# SFP_TEMP_EEPROM_GPIO.net
KiCad netlist of a schematic drawn in Altium Designer
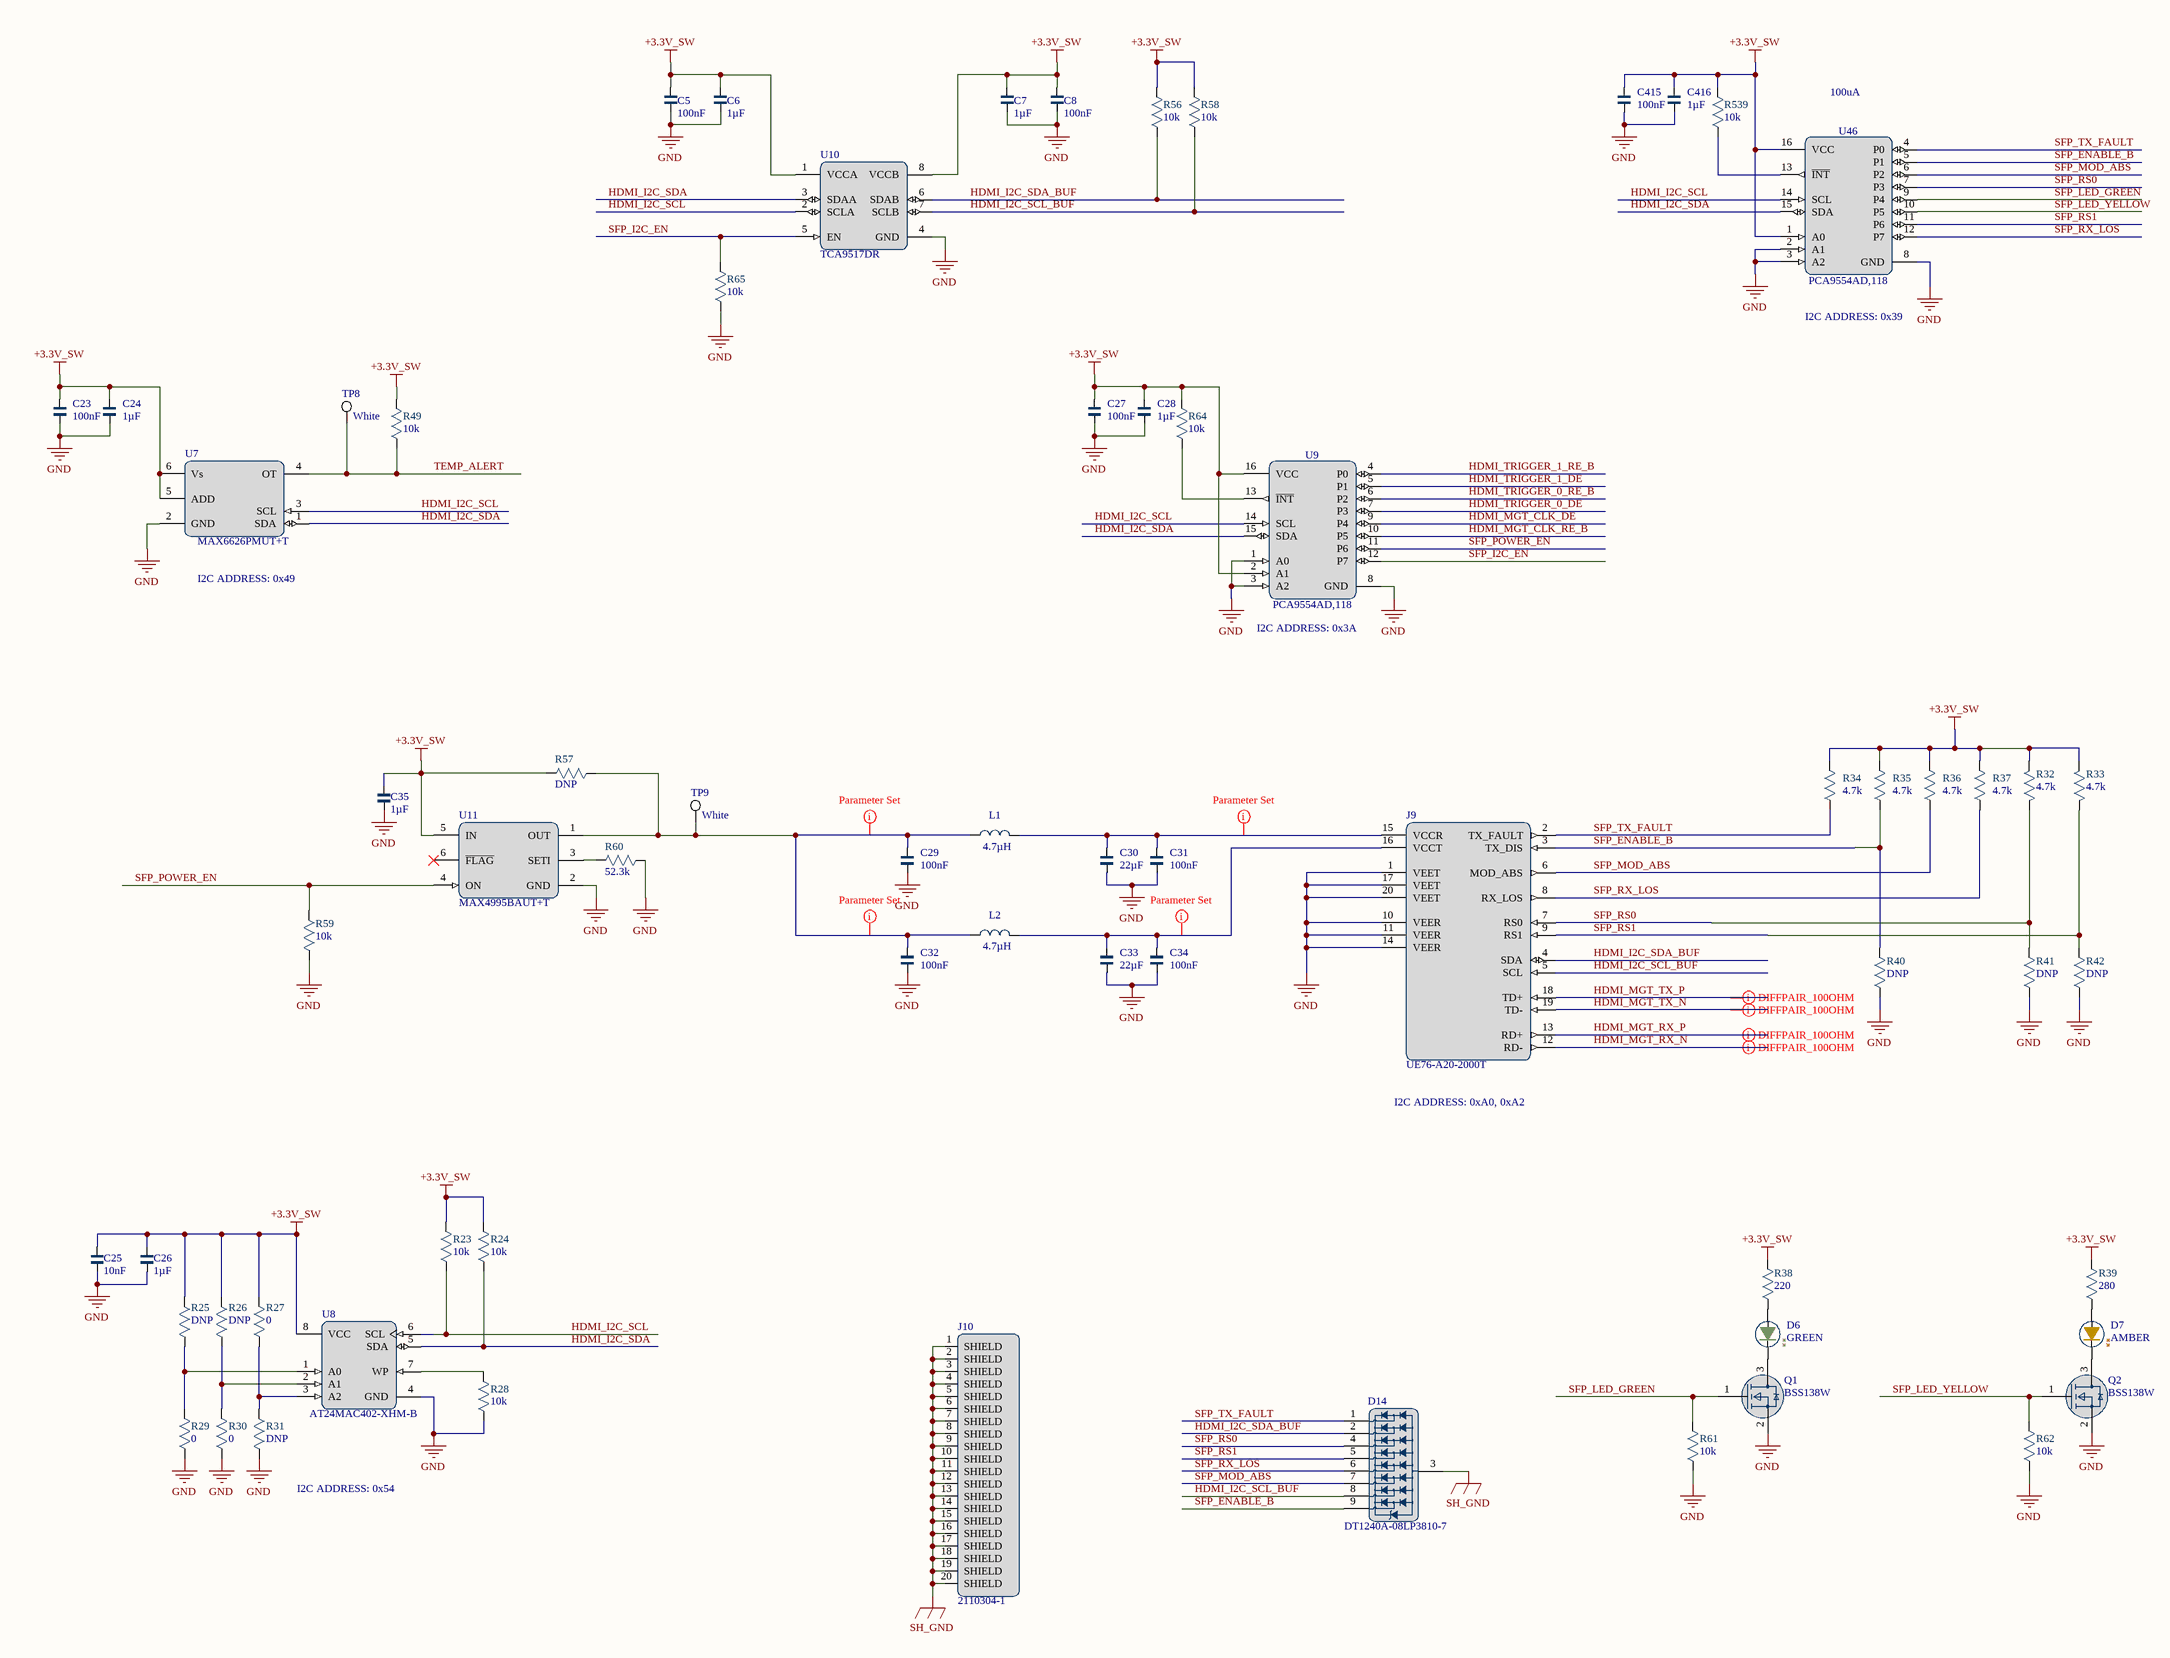
[diagram p0: SFP_TEMP_EEPROM_GPIO.SchDoc]

(export (version "E")
  (design (tool "Eeschema 10.0.6"))
  (components
    (comp (ref "C5")
      (value "100nF")
      (footprint "CAPC160X80X95L35")
      (description "CAP CER 0.1UF 25V X7R 0603")
      (fields (field (name "VOLTAGE") "25V") (field (name "MFG") "Kemet"))
      (libsource (lib "Atom Computing") (part "CAP"))
    )
    (comp (ref "C6")
      (value "1µF")
      (footprint "CAPC160X80X95L35")
      (description "CAP CER 1uF 10V 10% 0603")
      (fields (field (name "VOLTAGE") "10V") (field (name "TOLERANCE") "10%"))
      (libsource (lib "Atom Computing") (part "CAP"))
    )
    (comp (ref "C7")
      (value "1µF")
      (footprint "CAPC160X80X95L35")
      (description "CAP CER 1uF 10V 10% 0603")
      (fields (field (name "VOLTAGE") "10V") (field (name "TOLERANCE") "10%"))
      (libsource (lib "") (part "CAP_1"))
    )
    (comp (ref "C8")
      (value "100nF")
      (footprint "CAPC160X80X95L35")
      (description "CAP CER 0.1UF 25V X7R 0603")
      (fields (field (name "VOLTAGE") "25V") (field (name "MFG") "Kemet"))
      (libsource (lib "") (part "CAP_1"))
    )
    (comp (ref "C23")
      (value "100nF")
      (footprint "CAPC160X80X95L35")
      (description "CAP CER 0.1UF 25V X7R 0603")
      (fields (field (name "VOLTAGE") "25V") (field (name "MFG") "Kemet"))
      (libsource (lib "Atom Computing") (part "CAP"))
    )
    (comp (ref "C24")
      (value "1µF")
      (footprint "CAPC160X80X95L35")
      (description "CAP CER 1uF 10V 10% 0603")
      (fields (field (name "VOLTAGE") "10V") (field (name "TOLERANCE") "10%"))
      (libsource (lib "Atom Computing") (part "CAP"))
    )
    (comp (ref "C25")
      (value "10nF")
      (footprint "CAPC160X80X95L35")
      (description "CAP CER 10000PF 50V C0G 0603")
      (fields (field (name "MFG") "TDK Corporation") (field (name "TOLERANCE") "5%"))
      (libsource (lib "Atom Computing") (part "CAP"))
    )
    (comp (ref "C26")
      (value "1µF")
      (footprint "CAPC160X80X95L35")
      (description "CAP CER 1uF 10V 10% 0603")
      (fields (field (name "MFG") "Kemet") (field (name "TOLERANCE") "10%"))
      (libsource (lib "Atom Computing") (part "CAP"))
    )
    (comp (ref "C27")
      (value "100nF")
      (footprint "CAPC160X80X95L35")
      (description "CAP CER 0.1UF 25V X7R 0603")
      (fields (field (name "VOLTAGE") "25V") (field (name "MFG") "Kemet"))
      (libsource (lib "Atom Computing") (part "CAP"))
    )
    (comp (ref "C28")
      (value "1µF")
      (footprint "CAPC160X80X95L35")
      (description "CAP CER 1uF 10V 10% 0603")
      (fields (field (name "VOLTAGE") "10V") (field (name "TOLERANCE") "10%"))
      (libsource (lib "Atom Computing") (part "CAP"))
    )
    (comp (ref "C29")
      (value "100nF")
      (footprint "CAPC160X80X95L35")
      (description "CAP CER 0.1UF 25V X7R 0603")
      (fields (field (name "MFG") "Kemet") (field (name "TOLERANCE") "10%"))
      (libsource (lib "Atom Computing") (part "CAP"))
    )
    (comp (ref "C30")
      (value "22µF")
      (footprint "CAPC320X160X90L50")
      (description "CAP CER 22UF 10V X7R 1206")
      (fields (field (name "MFG") "MURATA") (field (name "TOLERANCE") "10%"))
      (libsource (lib "Atom Computing") (part "CAP"))
    )
    (comp (ref "C31")
      (value "100nF")
      (footprint "CAPC160X80X95L35")
      (description "CAP CER 0.1UF 25V X7R 0603")
      (fields (field (name "MFG") "Kemet") (field (name "TOLERANCE") "10%"))
      (libsource (lib "Atom Computing") (part "CAP"))
    )
    (comp (ref "C32")
      (value "100nF")
      (footprint "CAPC160X80X95L35")
      (description "CAP CER 0.1UF 25V X7R 0603")
      (fields (field (name "MFG") "Kemet") (field (name "TOLERANCE") "10%"))
      (libsource (lib "Atom Computing") (part "CAP"))
    )
    (comp (ref "C33")
      (value "22µF")
      (footprint "CAPC320X160X90L50")
      (description "CAP CER 22UF 10V X7R 1206")
      (fields (field (name "MFG") "MURATA") (field (name "TOLERANCE") "10%"))
      (libsource (lib "Atom Computing") (part "CAP"))
    )
    (comp (ref "C34")
      (value "100nF")
      (footprint "CAPC160X80X95L35")
      (description "CAP CER 0.1UF 25V X7R 0603")
      (fields (field (name "MFG") "Kemet") (field (name "TOLERANCE") "10%"))
      (libsource (lib "Atom Computing") (part "CAP"))
    )
    (comp (ref "C35")
      (value "1µF")
      (footprint "CAPC160X80X95L35")
      (description "CAP CER 1uF 10V 10% 0603")
      (fields (field (name "MFG") "Kemet") (field (name "TOLERANCE") "10%"))
      (libsource (lib "Atom Computing") (part "CAP"))
    )
    (comp (ref "C415")
      (value "100nF")
      (footprint "CAPC160X80X95L35")
      (description "CAP CER 0.1UF 25V X7R 0603")
      (fields (field (name "MFG") "Kemet") (field (name "TOLERANCE") "10%"))
      (libsource (lib "Atom Computing") (part "CAP"))
    )
    (comp (ref "C416")
      (value "1µF")
      (footprint "CAPC160X80X95L35")
      (description "±10% 35V Ceramic Capacitor X7R 0603 (1608 Metric)")
      (fields (field (name "MFG") "TDK Corporation"))
      (libsource (lib "") (part "CAP_2"))
    )
    (comp (ref "D6")
      (value "GREEN")
      (footprint "BROADCOM_HSMX-C120")
      (description "LED GREEN CLEAR CHIP SMD R/A")
      (fields (field (name "MFG") "AVAGO TECHNOLOGIES"))
      (libsource (lib "Atom Computing") (part "LED_GREEN"))
    )
    (comp (ref "D7")
      (value "AMBER")
      (footprint "BROADCOM_HSMX-C120")
      (description "LED AMBER CLEAR CHIP SMD R/A 0603")
      (fields (field (name "MFG") "Broadcom Limited"))
      (libsource (lib "Atom Computing") (part "LED_AMBER"))
    )
    (comp (ref "D14")
      (value "DT1240A-08LP3810-7")
      (footprint "DIODES_DT1240A-08LP3810-7")
      (description "TVS DIODE 3.3VWM 10V U-DFN3810-9")
      (fields (field (name "MFG") "Diodes Incorporated"))
      (libsource (lib "Atom Computing") (part "DT1240A-08LP3810-7"))
    )
    (comp (ref "J9")
      (value "UE76-A20-2000T")
      (footprint "AMPHENOL_UX76-A20-X00XX")
      (description "20 Position SFP+ Receptacle Connector Solder Surface Mount, Right Angle")
      (fields (field (name "MFG") "Amphenol ICC (Commercial Products)"))
      (libsource (lib "Atom Computing") (part "SFP+ Connector"))
    )
    (comp (ref "J10")
      (value "2110304-1")
      (footprint "TE_2110304-1_NO_KEEPOUT")
      (description "Position SFP+ Cage Connector Solder Through Hole, Right Angle")
      (fields (field (name "MFG") "TE Connectivity AMP Connectors"))
      (libsource (lib "Atom Computing") (part "2110304-1"))
    )
    (comp (ref "L1")
      (value "4.7µH")
      (footprint "VISHAY_IHLP-2020BZ")
      (description "FIXED IND 4.7UH 3.2A 81.3 MOHM")
      (fields (field (name "MFG") "Vishay Dale") (field (name "TOLERANCE") "20%"))
      (libsource (lib "Atom Computing") (part "IND"))
    )
    (comp (ref "L2")
      (value "4.7µH")
      (footprint "VISHAY_IHLP-2020BZ")
      (description "FIXED IND 4.7UH 3.2A 81.3 MOHM")
      (fields (field (name "MFG") "Vishay Dale") (field (name "TOLERANCE") "20%"))
      (libsource (lib "Atom Computing") (part "IND"))
    )
    (comp (ref "Q1")
      (value "BSS138W")
      (footprint "SOT23-3P65_210X110L36X22")
      (description "MOSFET N-CH 50V 210MA SC70")
      (fields (field (name "VOLTAGE") "50V") (field (name "MFG") "ON SEMICONDUCTOR"))
      (libsource (lib "Atom Computing") (part "FET_N_3PIN"))
    )
    (comp (ref "Q2")
      (value "BSS138W")
      (footprint "SOT23-3P65_210X110L36X22")
      (description "MOSFET N-CH 50V 210MA SC70")
      (fields (field (name "VOLTAGE") "50V") (field (name "MFG") "ON SEMICONDUCTOR"))
      (libsource (lib "Atom Computing") (part "FET_N_3PIN"))
    )
    (comp (ref "R23")
      (value "10k")
      (footprint "RESC160X85X55L30")
      (description "RES SMD 10K OHM 1% 1/10W 0603")
      (fields (field (name "MFG") "Panasonic Electronic Components") (field (name "POWER") "100mW"))
      (libsource (lib "Atom Computing") (part "RES"))
    )
    (comp (ref "R24")
      (value "10k")
      (footprint "RESC160X85X55L30")
      (description "RES SMD 10K OHM 1% 1/10W 0603")
      (fields (field (name "MFG") "Panasonic Electronic Components") (field (name "POWER") "100mW"))
      (libsource (lib "Atom Computing") (part "RES"))
    )
    (comp (ref "R25")
      (value "DNP")
      (footprint "RESC160X85X55L30")
      (description "DNP, RES 0603")
      (libsource (lib "Atom Computing") (part "RES"))
    )
    (comp (ref "R26")
      (value "DNP")
      (footprint "RESC160X85X55L30")
      (description "DNP, RES 0603")
      (libsource (lib "Atom Computing") (part "RES"))
    )
    (comp (ref "R27")
      (value "0")
      (footprint "RESC160X85X55L30")
      (description "RES 0 OHM JUMPER 1/10W 0603")
      (fields (field (name "MFG") "Yageo"))
      (libsource (lib "Atom Computing") (part "RES"))
    )
    (comp (ref "R28")
      (value "10k")
      (footprint "RESC160X85X55L30")
      (description "RES SMD 10K OHM 1% 1/10W 0603")
      (fields (field (name "MFG") "Panasonic Electronic Components") (field (name "POWER") "100mW"))
      (libsource (lib "Atom Computing") (part "RES"))
    )
    (comp (ref "R29")
      (value "0")
      (footprint "RESC160X85X55L30")
      (description "RES 0 OHM JUMPER 1/10W 0603")
      (fields (field (name "MFG") "Yageo"))
      (libsource (lib "Atom Computing") (part "RES"))
    )
    (comp (ref "R30")
      (value "0")
      (footprint "RESC160X85X55L30")
      (description "RES 0 OHM JUMPER 1/10W 0603")
      (fields (field (name "MFG") "Yageo"))
      (libsource (lib "Atom Computing") (part "RES"))
    )
    (comp (ref "R31")
      (value "DNP")
      (footprint "RESC160X85X55L30")
      (description "DNP, RES 0603")
      (libsource (lib "Atom Computing") (part "RES"))
    )
    (comp (ref "R32")
      (value "4.7k")
      (footprint "RESC160X85X55L30")
      (description "RES SMD 4.7K OHM 1% 1/10W 0603")
      (fields (field (name "MFG") "Yageo"))
      (libsource (lib "Atom Computing") (part "RES"))
    )
    (comp (ref "R33")
      (value "4.7k")
      (footprint "RESC160X85X55L30")
      (description "RES SMD 4.7K OHM 1% 1/10W 0603")
      (fields (field (name "MFG") "Yageo"))
      (libsource (lib "Atom Computing") (part "RES"))
    )
    (comp (ref "R34")
      (value "4.7k")
      (footprint "RESC160X85X55L30")
      (description "RES SMD 4.7K OHM 1% 1/10W 0603")
      (fields (field (name "MFG") "Yageo"))
      (libsource (lib "Atom Computing") (part "RES"))
    )
    (comp (ref "R35")
      (value "4.7k")
      (footprint "RESC160X85X55L30")
      (description "RES SMD 4.7K OHM 1% 1/10W 0603")
      (fields (field (name "MFG") "Yageo"))
      (libsource (lib "Atom Computing") (part "RES"))
    )
    (comp (ref "R36")
      (value "4.7k")
      (footprint "RESC160X85X55L30")
      (description "RES SMD 4.7K OHM 1% 1/10W 0603")
      (fields (field (name "MFG") "Yageo"))
      (libsource (lib "Atom Computing") (part "RES"))
    )
    (comp (ref "R37")
      (value "4.7k")
      (footprint "RESC160X85X55L30")
      (description "RES SMD 4.7K OHM 1% 1/10W 0603")
      (fields (field (name "MFG") "Yageo"))
      (libsource (lib "Atom Computing") (part "RES"))
    )
    (comp (ref "R38")
      (value "220")
      (footprint "RESC160X85X55L30")
      (description "RES SMD 220 OHM 1% 1/10W 0603")
      (fields (field (name "MFG") "Yageo"))
      (libsource (lib "Atom Computing") (part "RES"))
    )
    (comp (ref "R39")
      (value "280")
      (footprint "RESC160X85X55L30")
      (description "RES SMD 280 OHM 1% 1/10W 0603")
      (fields (field (name "MFG") "Panasonic Electronic Components") (field (name "POWER") "100mW"))
      (libsource (lib "Atom Computing") (part "RES"))
    )
    (comp (ref "R40")
      (value "DNP")
      (footprint "RESC160X85X55L30")
      (description "DNP, RES 0603")
      (libsource (lib "Atom Computing") (part "RES"))
    )
    (comp (ref "R41")
      (value "DNP")
      (footprint "RESC160X85X55L30")
      (description "DNP, RES 0603")
      (libsource (lib "Atom Computing") (part "RES"))
    )
    (comp (ref "R42")
      (value "DNP")
      (footprint "RESC160X85X55L30")
      (description "DNP, RES 0603")
      (libsource (lib "Atom Computing") (part "RES"))
    )
    (comp (ref "R49")
      (value "10k")
      (footprint "RESC160X85X55L30")
      (description "RES SMD 10K OHM 1% 1/10W 0603")
      (fields (field (name "MFG") "Panasonic Electronic Components") (field (name "POWER") "100mW"))
      (libsource (lib "Atom Computing") (part "RES"))
    )
    (comp (ref "R56")
      (value "10k")
      (footprint "RESC160X85X55L30")
      (description "RES SMD 10K OHM 1% 1/10W 0603")
      (fields (field (name "MFG") "Panasonic Electronic Components") (field (name "POWER") "100mW"))
      (libsource (lib "Atom Computing") (part "RES"))
    )
    (comp (ref "R57")
      (value "DNP")
      (footprint "RESC160X85X55L30")
      (description "DNP, RES 0603")
      (libsource (lib "Atom Computing") (part "RES"))
    )
    (comp (ref "R58")
      (value "10k")
      (footprint "RESC160X85X55L30")
      (description "RES SMD 10K OHM 1% 1/10W 0603")
      (fields (field (name "MFG") "Panasonic Electronic Components") (field (name "POWER") "100mW"))
      (libsource (lib "Atom Computing") (part "RES"))
    )
    (comp (ref "R59")
      (value "10k")
      (footprint "RESC160X85X55L30")
      (description "RES SMD 10K OHM 1% 1/10W 0603")
      (fields (field (name "MFG") "Panasonic Electronic Components") (field (name "POWER") "100mW"))
      (libsource (lib "Atom Computing") (part "RES"))
    )
    (comp (ref "R60")
      (value "52.3k")
      (footprint "RESC160X85X55L30")
      (description "RES SMD 52.3K 0.1% 1/10W 0603")
      (fields (field (name "MFG") "Yageo"))
      (libsource (lib "Atom Computing") (part "RES"))
    )
    (comp (ref "R61")
      (value "10k")
      (footprint "RESC160X85X55L30")
      (description "RES SMD 10K OHM 1% 1/10W 0603")
      (fields (field (name "MFG") "Panasonic Electronic Components") (field (name "POWER") "100mW"))
      (libsource (lib "Atom Computing") (part "RES"))
    )
    (comp (ref "R62")
      (value "10k")
      (footprint "RESC160X85X55L30")
      (description "RES SMD 10K OHM 1% 1/10W 0603")
      (fields (field (name "MFG") "Panasonic Electronic Components") (field (name "POWER") "100mW"))
      (libsource (lib "Atom Computing") (part "RES"))
    )
    (comp (ref "R64")
      (value "10k")
      (footprint "RESC160X85X55L30")
      (description "RES SMD 10K OHM 1% 1/10W 0603")
      (fields (field (name "MFG") "Panasonic Electronic Components") (field (name "POWER") "100mW"))
      (libsource (lib "Atom Computing") (part "RES"))
    )
    (comp (ref "R65")
      (value "10k")
      (footprint "RESC160X85X55L30")
      (description "RES SMD 10K OHM 1% 1/10W 0603")
      (fields (field (name "MFG") "Panasonic Electronic Components") (field (name "POWER") "100mW"))
      (libsource (lib "Atom Computing") (part "RES"))
    )
    (comp (ref "R539")
      (value "10k")
      (footprint "RESC160X85X55L30")
      (description "RES SMD 10K OHM 1% 1/10W 0603")
      (fields (field (name "MFG") "Panasonic Electronic Components") (field (name "POWER") "100mW"))
      (libsource (lib "Atom Computing") (part "RES"))
    )
    (comp (ref "TP8")
      (value "White")
      (footprint "Keystone_5002")
      (description "Test Point, White, 1-Pin THD, RoHS, Bulk")
      (fields (field (name "MFG") "Keystone"))
      (libsource (lib "Atom Computing") (part "TP_WHITE"))
    )
    (comp (ref "TP9")
      (value "White")
      (footprint "Keystone_5002")
      (description "Test Point, White, 1-Pin THD, RoHS, Bulk")
      (fields (field (name "MFG") "Keystone"))
      (libsource (lib "Atom Computing") (part "TP_WHITE"))
    )
    (comp (ref "U7")
      (value "MAX6626PMUT+T")
      (footprint "SOT23-6P95_280X145L45X42")
      (description "Temperature Sensor Digital, Local -55°C ~ 125°C 12 b SOT-6")
      (fields (field (name "MFG") "Maxim"))
      (libsource (lib "Atom Computing") (part "MAX6626xxUT"))
    )
    (comp (ref "U8")
      (value "AT24MAC402-XHM-B")
      (footprint "SOP8P65_300X640X120L60X24")
      (description "IC EEPROM  MAC 48 2KBIT I2C 1MHZ 8TSSOP")
      (fields (field (name "MFG") "Microchip Technology"))
      (libsource (lib "Atom Computing") (part "AT24MAC402_8PIN"))
    )
    (comp (ref "U9")
      (value "PCA9554AD,118")
      (footprint "SOIC16P127_1030X1032X265L83X42")
      (description "I/O GPIO Expander 8 I2C, SMBus 400 kHz 16-SO")
      (fields (field (name "MFG") "NXP USA Inc."))
      (libsource (lib "Atom Computing") (part "PCA9554xD/PW"))
    )
    (comp (ref "U10")
      (value "TCA9517DR")
      (footprint "SOIC8P127_490X599X175L84X41")
      (description "Voltage Level Translator Bidirectional 1 Circuit 2 Channel 8-SOIC")
      (fields (field (name "MFG") "Texas Instruments"))
      (libsource (lib "Atom Computing") (part "TCA9517"))
    )
    (comp (ref "U11")
      (value "MAX4995BAUT+T")
      (footprint "SOT23-6P95_280X145L45X42")
      (description "IC CURRENT SWITCH ADJ 10% SOT-23-6")
      (fields (field (name "MFG") "Analog Devices Inc./Maxim Integrated"))
      (libsource (lib "Atom Computing") (part "MAX4995xAUT"))
    )
    (comp (ref "U46")
      (value "PCA9554AD,118")
      (footprint "SOIC16P127_1030X1032X265L83X42")
      (description "I/O GPIO Expander 8 I2C, SMBus 400 kHz 16-SO")
      (fields (field (name "MFG") "NXP USA Inc."))
      (libsource (lib "Atom Computing") (part "PCA9554xD/PW"))
    )
  )
  (nets
    (net (code "1") (name "+3.3V_SW") (class "Default")
      (node (ref "C23") (pin "1") (pinfunction "1_1") (pintype "passive"))
      (node (ref "C24") (pin "1") (pinfunction "1_1") (pintype "passive"))
      (node (ref "C25") (pin "1") (pinfunction "1_1") (pintype "passive"))
      (node (ref "C26") (pin "1") (pinfunction "1_1") (pintype "passive"))
      (node (ref "C27") (pin "1") (pinfunction "1_1") (pintype "passive"))
      (node (ref "C28") (pin "1") (pinfunction "1_1") (pintype "passive"))
      (node (ref "C35") (pin "1") (pinfunction "1_1") (pintype "passive"))
      (node (ref "C415") (pin "1") (pinfunction "1_1") (pintype "passive"))
      (node (ref "C416") (pin "2") (pinfunction "2_2") (pintype "passive"))
      (node (ref "C5") (pin "1") (pinfunction "1_1") (pintype "passive"))
      (node (ref "C6") (pin "1") (pinfunction "1_1") (pintype "passive"))
      (node (ref "C7") (pin "1") (pinfunction "1_1") (pintype "passive"))
      (node (ref "C8") (pin "1") (pinfunction "1_1") (pintype "passive"))
      (node (ref "R23") (pin "2") (pinfunction "2_2") (pintype "passive"))
      (node (ref "R24") (pin "2") (pinfunction "2_2") (pintype "passive"))
      (node (ref "R25") (pin "1") (pinfunction "1_1") (pintype "passive"))
      (node (ref "R26") (pin "1") (pinfunction "1_1") (pintype "passive"))
      (node (ref "R27") (pin "2") (pinfunction "2_2") (pintype "passive"))
      (node (ref "R32") (pin "2") (pinfunction "2_2") (pintype "passive"))
      (node (ref "R33") (pin "2") (pinfunction "2_2") (pintype "passive"))
      (node (ref "R34") (pin "2") (pinfunction "2_2") (pintype "passive"))
      (node (ref "R35") (pin "2") (pinfunction "2_2") (pintype "passive"))
      (node (ref "R36") (pin "2") (pinfunction "2_2") (pintype "passive"))
      (node (ref "R37") (pin "2") (pinfunction "2_2") (pintype "passive"))
      (node (ref "R38") (pin "2") (pinfunction "2_2") (pintype "passive"))
      (node (ref "R39") (pin "2") (pinfunction "2_2") (pintype "passive"))
      (node (ref "R49") (pin "2") (pinfunction "2_2") (pintype "passive"))
      (node (ref "R539") (pin "2") (pinfunction "2_2") (pintype "passive"))
      (node (ref "R56") (pin "2") (pinfunction "2_2") (pintype "passive"))
      (node (ref "R57") (pin "2") (pinfunction "2_2") (pintype "passive"))
      (node (ref "R58") (pin "2") (pinfunction "2_2") (pintype "passive"))
      (node (ref "R64") (pin "2") (pinfunction "2_2") (pintype "passive"))
      (node (ref "U10") (pin "1") (pinfunction "VCCA_1") (pintype "power_in"))
      (node (ref "U10") (pin "8") (pinfunction "VCCB_8") (pintype "power_in"))
      (node (ref "U11") (pin "5") (pinfunction "IN_5") (pintype "passive"))
      (node (ref "U46") (pin "1") (pinfunction "A0_1") (pintype "input"))
      (node (ref "U46") (pin "16") (pinfunction "VCC_16") (pintype "power_in"))
      (node (ref "U7") (pin "5") (pinfunction "ADD_5") (pintype "passive"))
      (node (ref "U7") (pin "6") (pinfunction "Vs_6") (pintype "power_in"))
      (node (ref "U8") (pin "8") (pinfunction "VCC_8") (pintype "power_in"))
      (node (ref "U9") (pin "16") (pinfunction "VCC_16") (pintype "power_in"))
      (node (ref "U9") (pin "2") (pinfunction "A1_2") (pintype "input"))
    )
    (net (code "2") (name "/HDMI_I2C_SCL") (class "Default")
      (node (ref "R23") (pin "1") (pinfunction "1_1") (pintype "passive"))
      (node (ref "U10") (pin "2") (pinfunction "SCLA_2") (pintype "bidirectional"))
      (node (ref "U46") (pin "14") (pinfunction "SCL_14") (pintype "input"))
      (node (ref "U7") (pin "3") (pinfunction "SCL_3") (pintype "input"))
      (node (ref "U8") (pin "6") (pinfunction "SCL_6") (pintype "input"))
      (node (ref "U9") (pin "14") (pinfunction "SCL_14") (pintype "input"))
    )
    (net (code "3") (name "/HDMI_I2C_SCL_BUF") (class "Default")
      (node (ref "D14") (pin "8") (pinfunction "LINE-4_8") (pintype "passive"))
      (node (ref "J9") (pin "5") (pinfunction "SCL_5") (pintype "input"))
      (node (ref "R58") (pin "1") (pinfunction "1_1") (pintype "passive"))
      (node (ref "U10") (pin "7") (pinfunction "SCLB_7") (pintype "bidirectional"))
    )
    (net (code "4") (name "/HDMI_I2C_SDA") (class "Default")
      (node (ref "R24") (pin "1") (pinfunction "1_1") (pintype "passive"))
      (node (ref "U10") (pin "3") (pinfunction "SDAA_3") (pintype "bidirectional"))
      (node (ref "U46") (pin "15") (pinfunction "SDA_15") (pintype "bidirectional"))
      (node (ref "U7") (pin "1") (pinfunction "SDA_1") (pintype "bidirectional"))
      (node (ref "U8") (pin "5") (pinfunction "SDA_5") (pintype "bidirectional"))
      (node (ref "U9") (pin "15") (pinfunction "SDA_15") (pintype "bidirectional"))
    )
    (net (code "5") (name "/HDMI_I2C_SDA_BUF") (class "Default")
      (node (ref "D14") (pin "2") (pinfunction "LINE-3_2") (pintype "passive"))
      (node (ref "J9") (pin "4") (pinfunction "SDA_4") (pintype "bidirectional"))
      (node (ref "R56") (pin "1") (pinfunction "1_1") (pintype "passive"))
      (node (ref "U10") (pin "6") (pinfunction "SDAB_6") (pintype "bidirectional"))
    )
    (net (code "6") (name "/HDMI_MGT_CLK_DE") (class "Default")
      (node (ref "U9") (pin "9") (pinfunction "P4_9") (pintype "bidirectional"))
    )
    (net (code "7") (name "/HDMI_MGT_CLK_RE_B") (class "Default")
      (node (ref "U9") (pin "10") (pinfunction "P5_10") (pintype "bidirectional"))
    )
    (net (code "8") (name "/HDMI_MGT_RX_N") (class "Default")
      (node (ref "J9") (pin "12") (pinfunction "RD-_12") (pintype "output"))
    )
    (net (code "9") (name "/HDMI_MGT_RX_P") (class "Default")
      (node (ref "J9") (pin "13") (pinfunction "RD+_13") (pintype "output"))
    )
    (net (code "10") (name "/HDMI_MGT_TX_N") (class "Default")
      (node (ref "J9") (pin "19") (pinfunction "TD-_19") (pintype "input"))
    )
    (net (code "11") (name "/HDMI_MGT_TX_P") (class "Default")
      (node (ref "J9") (pin "18") (pinfunction "TD+_18") (pintype "input"))
    )
    (net (code "12") (name "/HDMI_TRIGGER_0_DE") (class "Default")
      (node (ref "U9") (pin "7") (pinfunction "P3_7") (pintype "bidirectional"))
    )
    (net (code "13") (name "/HDMI_TRIGGER_0_RE_B") (class "Default")
      (node (ref "U9") (pin "6") (pinfunction "P2_6") (pintype "bidirectional"))
    )
    (net (code "14") (name "/HDMI_TRIGGER_1_DE") (class "Default")
      (node (ref "U9") (pin "5") (pinfunction "P1_5") (pintype "bidirectional"))
    )
    (net (code "15") (name "/HDMI_TRIGGER_1_RE_B") (class "Default")
      (node (ref "U9") (pin "4") (pinfunction "P0_4") (pintype "bidirectional"))
    )
    (net (code "16") (name "/SFP_ENABLE_B") (class "Default")
      (node (ref "D14") (pin "9") (pinfunction "LINE-2_9") (pintype "passive"))
      (node (ref "J9") (pin "3") (pinfunction "TX_DIS_3") (pintype "input"))
      (node (ref "R35") (pin "1") (pinfunction "1_1") (pintype "passive"))
      (node (ref "R40") (pin "2") (pinfunction "2_2") (pintype "passive"))
      (node (ref "U46") (pin "5") (pinfunction "P1_5") (pintype "bidirectional"))
    )
    (net (code "17") (name "/SFP_I2C_EN") (class "Default")
      (node (ref "R65") (pin "2") (pinfunction "2_2") (pintype "passive"))
      (node (ref "U10") (pin "5") (pinfunction "EN_5") (pintype "input"))
      (node (ref "U9") (pin "12") (pinfunction "P7_12") (pintype "bidirectional"))
    )
    (net (code "18") (name "/SFP_LED_GREEN") (class "Default")
      (node (ref "Q1") (pin "1") (pinfunction "GATE_1") (pintype "passive"))
      (node (ref "R61") (pin "2") (pinfunction "2_2") (pintype "passive"))
      (node (ref "U46") (pin "9") (pinfunction "P4_9") (pintype "bidirectional"))
    )
    (net (code "19") (name "/SFP_LED_YELLOW") (class "Default")
      (node (ref "Q2") (pin "1") (pinfunction "GATE_1") (pintype "passive"))
      (node (ref "R62") (pin "2") (pinfunction "2_2") (pintype "passive"))
      (node (ref "U46") (pin "10") (pinfunction "P5_10") (pintype "bidirectional"))
    )
    (net (code "20") (name "/SFP_MOD_ABS") (class "Default")
      (node (ref "D14") (pin "7") (pinfunction "LINE-5_7") (pintype "passive"))
      (node (ref "J9") (pin "6") (pinfunction "MOD_ABS_6") (pintype "output"))
      (node (ref "R36") (pin "1") (pinfunction "1_1") (pintype "passive"))
      (node (ref "U46") (pin "6") (pinfunction "P2_6") (pintype "bidirectional"))
    )
    (net (code "21") (name "/SFP_POWER_EN") (class "Default")
      (node (ref "R59") (pin "1") (pinfunction "1_1") (pintype "passive"))
      (node (ref "U11") (pin "4") (pinfunction "ON_4") (pintype "input"))
      (node (ref "U9") (pin "11") (pinfunction "P6_11") (pintype "bidirectional"))
    )
    (net (code "22") (name "/SFP_RS0") (class "Default")
      (node (ref "D14") (pin "4") (pinfunction "LINE-6_4") (pintype "passive"))
      (node (ref "J9") (pin "7") (pinfunction "RS0_7") (pintype "input"))
      (node (ref "R32") (pin "1") (pinfunction "1_1") (pintype "passive"))
      (node (ref "R41") (pin "2") (pinfunction "2_2") (pintype "passive"))
      (node (ref "U46") (pin "7") (pinfunction "P3_7") (pintype "bidirectional"))
    )
    (net (code "23") (name "/SFP_RS1") (class "Default")
      (node (ref "D14") (pin "5") (pinfunction "LINE-8_5") (pintype "passive"))
      (node (ref "J9") (pin "9") (pinfunction "RS1_9") (pintype "input"))
      (node (ref "R33") (pin "1") (pinfunction "1_1") (pintype "passive"))
      (node (ref "R42") (pin "2") (pinfunction "2_2") (pintype "passive"))
      (node (ref "U46") (pin "11") (pinfunction "P6_11") (pintype "bidirectional"))
    )
    (net (code "24") (name "/SFP_RX_LOS") (class "Default")
      (node (ref "D14") (pin "6") (pinfunction "LINE-7_6") (pintype "passive"))
      (node (ref "J9") (pin "8") (pinfunction "RX_LOS_8") (pintype "output"))
      (node (ref "R37") (pin "1") (pinfunction "1_1") (pintype "passive"))
      (node (ref "U46") (pin "12") (pinfunction "P7_12") (pintype "bidirectional"))
    )
    (net (code "25") (name "/SFP_TX_FAULT") (class "Default")
      (node (ref "D14") (pin "1") (pinfunction "LINE-1_1") (pintype "passive"))
      (node (ref "J9") (pin "2") (pinfunction "TX_FAULT_2") (pintype "output"))
      (node (ref "R34") (pin "1") (pinfunction "1_1") (pintype "passive"))
      (node (ref "U46") (pin "4") (pinfunction "P0_4") (pintype "bidirectional"))
    )
    (net (code "26") (name "/TEMP_ALERT") (class "Default")
      (node (ref "R49") (pin "1") (pinfunction "1_1") (pintype "passive"))
      (node (ref "TP8") (pin "1") (pinfunction "1_1") (pintype "passive"))
      (node (ref "U7") (pin "4") (pinfunction "OT_4") (pintype "open_collector"))
    )
    (net (code "27") (name "GND") (class "Default")
      (node (ref "C23") (pin "2") (pinfunction "2_2") (pintype "passive"))
      (node (ref "C24") (pin "2") (pinfunction "2_2") (pintype "passive"))
      (node (ref "C25") (pin "2") (pinfunction "2_2") (pintype "passive"))
      (node (ref "C26") (pin "2") (pinfunction "2_2") (pintype "passive"))
      (node (ref "C27") (pin "2") (pinfunction "2_2") (pintype "passive"))
      (node (ref "C28") (pin "2") (pinfunction "2_2") (pintype "passive"))
      (node (ref "C29") (pin "2") (pinfunction "2_2") (pintype "passive"))
      (node (ref "C30") (pin "2") (pinfunction "2_2") (pintype "passive"))
      (node (ref "C31") (pin "2") (pinfunction "2_2") (pintype "passive"))
      (node (ref "C32") (pin "2") (pinfunction "2_2") (pintype "passive"))
      (node (ref "C33") (pin "2") (pinfunction "2_2") (pintype "passive"))
      (node (ref "C34") (pin "2") (pinfunction "2_2") (pintype "passive"))
      (node (ref "C35") (pin "2") (pinfunction "2_2") (pintype "passive"))
      (node (ref "C415") (pin "2") (pinfunction "2_2") (pintype "passive"))
      (node (ref "C416") (pin "1") (pinfunction "1_1") (pintype "passive"))
      (node (ref "C5") (pin "2") (pinfunction "2_2") (pintype "passive"))
      (node (ref "C6") (pin "2") (pinfunction "2_2") (pintype "passive"))
      (node (ref "C7") (pin "2") (pinfunction "2_2") (pintype "passive"))
      (node (ref "C8") (pin "2") (pinfunction "2_2") (pintype "passive"))
      (node (ref "J9") (pin "1") (pinfunction "VEET_1") (pintype "power_in"))
      (node (ref "J9") (pin "10") (pinfunction "VEER_10") (pintype "power_in"))
      (node (ref "J9") (pin "11") (pinfunction "VEER_11") (pintype "power_in"))
      (node (ref "J9") (pin "14") (pinfunction "VEER_14") (pintype "power_in"))
      (node (ref "J9") (pin "17") (pinfunction "VEET_17") (pintype "power_in"))
      (node (ref "J9") (pin "20") (pinfunction "VEET_20") (pintype "power_in"))
      (node (ref "Q1") (pin "2") (pinfunction "SOURCE_2") (pintype "passive"))
      (node (ref "Q2") (pin "2") (pinfunction "SOURCE_2") (pintype "passive"))
      (node (ref "R28") (pin "1") (pinfunction "1_1") (pintype "passive"))
      (node (ref "R29") (pin "1") (pinfunction "1_1") (pintype "passive"))
      (node (ref "R30") (pin "1") (pinfunction "1_1") (pintype "passive"))
      (node (ref "R31") (pin "2") (pinfunction "2_2") (pintype "passive"))
      (node (ref "R40") (pin "1") (pinfunction "1_1") (pintype "passive"))
      (node (ref "R41") (pin "1") (pinfunction "1_1") (pintype "passive"))
      (node (ref "R42") (pin "1") (pinfunction "1_1") (pintype "passive"))
      (node (ref "R59") (pin "2") (pinfunction "2_2") (pintype "passive"))
      (node (ref "R60") (pin "1") (pinfunction "1_1") (pintype "passive"))
      (node (ref "R61") (pin "1") (pinfunction "1_1") (pintype "passive"))
      (node (ref "R62") (pin "1") (pinfunction "1_1") (pintype "passive"))
      (node (ref "R65") (pin "1") (pinfunction "1_1") (pintype "passive"))
      (node (ref "U10") (pin "4") (pinfunction "GND_4") (pintype "power_in"))
      (node (ref "U11") (pin "2") (pinfunction "GND_2") (pintype "passive"))
      (node (ref "U46") (pin "2") (pinfunction "A1_2") (pintype "input"))
      (node (ref "U46") (pin "3") (pinfunction "A2_3") (pintype "input"))
      (node (ref "U46") (pin "8") (pinfunction "GND_8") (pintype "power_in"))
      (node (ref "U7") (pin "2") (pinfunction "GND_2") (pintype "power_in"))
      (node (ref "U8") (pin "4") (pinfunction "GND_4") (pintype "power_in"))
      (node (ref "U9") (pin "1") (pinfunction "A0_1") (pintype "input"))
      (node (ref "U9") (pin "3") (pinfunction "A2_3") (pintype "input"))
      (node (ref "U9") (pin "8") (pinfunction "GND_8") (pintype "power_in"))
    )
    (net (code "28") (name "Net-(D6-Pad2)") (class "Default")
      (node (ref "D6") (pin "2") (pinfunction "2_2") (pintype "passive"))
      (node (ref "R38") (pin "1") (pinfunction "1_1") (pintype "passive"))
    )
    (net (code "29") (name "Net-(D7-Pad2)") (class "Default")
      (node (ref "D7") (pin "2") (pinfunction "2_2") (pintype "passive"))
      (node (ref "R39") (pin "1") (pinfunction "1_1") (pintype "passive"))
    )
    (net (code "30") (name "Net-(J9-VCCR)") (class "Default")
      (node (ref "C30") (pin "1") (pinfunction "1_1") (pintype "passive"))
      (node (ref "C31") (pin "1") (pinfunction "1_1") (pintype "passive"))
      (node (ref "J9") (pin "15") (pinfunction "VCCR_15") (pintype "power_in"))
      (node (ref "L1") (pin "2") (pinfunction "2_2") (pintype "passive"))
    )
    (net (code "31") (name "Net-(J9-VCCT)") (class "Default")
      (node (ref "C33") (pin "1") (pinfunction "1_1") (pintype "passive"))
      (node (ref "C34") (pin "1") (pinfunction "1_1") (pintype "passive"))
      (node (ref "J9") (pin "16") (pinfunction "VCCT_16") (pintype "power_in"))
      (node (ref "L2") (pin "2") (pinfunction "2_2") (pintype "passive"))
    )
    (net (code "32") (name "Net-(Q1-DRAIN)") (class "Default")
      (node (ref "D6") (pin "1") (pinfunction "1_1") (pintype "passive"))
      (node (ref "Q1") (pin "3") (pinfunction "DRAIN_3") (pintype "passive"))
    )
    (net (code "33") (name "Net-(Q2-DRAIN)") (class "Default")
      (node (ref "D7") (pin "1") (pinfunction "1_1") (pintype "passive"))
      (node (ref "Q2") (pin "3") (pinfunction "DRAIN_3") (pintype "passive"))
    )
    (net (code "34") (name "Net-(U8-A0)") (class "Default")
      (node (ref "R25") (pin "2") (pinfunction "2_2") (pintype "passive"))
      (node (ref "R29") (pin "2") (pinfunction "2_2") (pintype "passive"))
      (node (ref "U8") (pin "1") (pinfunction "A0_1") (pintype "input"))
    )
    (net (code "35") (name "Net-(U8-A1)") (class "Default")
      (node (ref "R26") (pin "2") (pinfunction "2_2") (pintype "passive"))
      (node (ref "R30") (pin "2") (pinfunction "2_2") (pintype "passive"))
      (node (ref "U8") (pin "2") (pinfunction "A1_2") (pintype "input"))
    )
    (net (code "36") (name "Net-(U8-A2)") (class "Default")
      (node (ref "R27") (pin "1") (pinfunction "1_1") (pintype "passive"))
      (node (ref "R31") (pin "1") (pinfunction "1_1") (pintype "passive"))
      (node (ref "U8") (pin "3") (pinfunction "A2_3") (pintype "input"))
    )
    (net (code "37") (name "Net-(U8-WP)") (class "Default")
      (node (ref "R28") (pin "2") (pinfunction "2_2") (pintype "passive"))
      (node (ref "U8") (pin "7") (pinfunction "WP_7") (pintype "input"))
    )
    (net (code "38") (name "Net-(U9-~{INT})") (class "Default")
      (node (ref "R64") (pin "1") (pinfunction "1_1") (pintype "passive"))
      (node (ref "U9") (pin "13") (pinfunction "~{INT}_13") (pintype "output"))
    )
    (net (code "39") (name "Net-(U11-OUT)") (class "Default")
      (node (ref "C29") (pin "1") (pinfunction "1_1") (pintype "passive"))
      (node (ref "C32") (pin "1") (pinfunction "1_1") (pintype "passive"))
      (node (ref "L1") (pin "1") (pinfunction "1_1") (pintype "passive"))
      (node (ref "L2") (pin "1") (pinfunction "1_1") (pintype "passive"))
      (node (ref "R57") (pin "1") (pinfunction "1_1") (pintype "passive"))
      (node (ref "TP9") (pin "1") (pinfunction "1_1") (pintype "passive"))
      (node (ref "U11") (pin "1") (pinfunction "OUT_1") (pintype "power_in"))
    )
    (net (code "40") (name "Net-(U11-SETI)") (class "Default")
      (node (ref "R60") (pin "2") (pinfunction "2_2") (pintype "passive"))
      (node (ref "U11") (pin "3") (pinfunction "SETI_3") (pintype "passive"))
    )
    (net (code "41") (name "Net-(U46-~{INT})") (class "Default")
      (node (ref "R539") (pin "1") (pinfunction "1_1") (pintype "passive"))
      (node (ref "U46") (pin "13") (pinfunction "~{INT}_13") (pintype "output"))
    )
    (net (code "42") (name "SH_GND") (class "Default")
      (node (ref "D14") (pin "3") (pinfunction "GND_3") (pintype "passive"))
      (node (ref "J10") (pin "1") (pinfunction "SHIELD_1") (pintype "passive"))
      (node (ref "J10") (pin "10") (pinfunction "SHIELD_10") (pintype "passive"))
      (node (ref "J10") (pin "11") (pinfunction "SHIELD_11") (pintype "passive"))
      (node (ref "J10") (pin "12") (pinfunction "SHIELD_12") (pintype "passive"))
      (node (ref "J10") (pin "13") (pinfunction "SHIELD_13") (pintype "passive"))
      (node (ref "J10") (pin "14") (pinfunction "SHIELD_14") (pintype "passive"))
      (node (ref "J10") (pin "15") (pinfunction "SHIELD_15") (pintype "passive"))
      (node (ref "J10") (pin "16") (pinfunction "SHIELD_16") (pintype "passive"))
      (node (ref "J10") (pin "17") (pinfunction "SHIELD_17") (pintype "passive"))
      (node (ref "J10") (pin "18") (pinfunction "SHIELD_18") (pintype "passive"))
      (node (ref "J10") (pin "19") (pinfunction "SHIELD_19") (pintype "passive"))
      (node (ref "J10") (pin "2") (pinfunction "SHIELD_2") (pintype "passive"))
      (node (ref "J10") (pin "20") (pinfunction "SHIELD_20") (pintype "passive"))
      (node (ref "J10") (pin "3") (pinfunction "SHIELD_3") (pintype "passive"))
      (node (ref "J10") (pin "4") (pinfunction "SHIELD_4") (pintype "passive"))
      (node (ref "J10") (pin "5") (pinfunction "SHIELD_5") (pintype "passive"))
      (node (ref "J10") (pin "6") (pinfunction "SHIELD_6") (pintype "passive"))
      (node (ref "J10") (pin "7") (pinfunction "SHIELD_7") (pintype "passive"))
      (node (ref "J10") (pin "8") (pinfunction "SHIELD_8") (pintype "passive"))
      (node (ref "J10") (pin "9") (pinfunction "SHIELD_9") (pintype "passive"))
    )
    (net (code "43") (name "unconnected-(U11-~{FLAG}-Pad6)") (class "Default")
      (node (ref "U11") (pin "6") (pinfunction "~{FLAG}_6") (pintype "power_in+no_connect"))
    )
  )
)
